# BW1097_EthernetSchDoc.net
KiCad netlist of a schematic drawn in Altium Designer
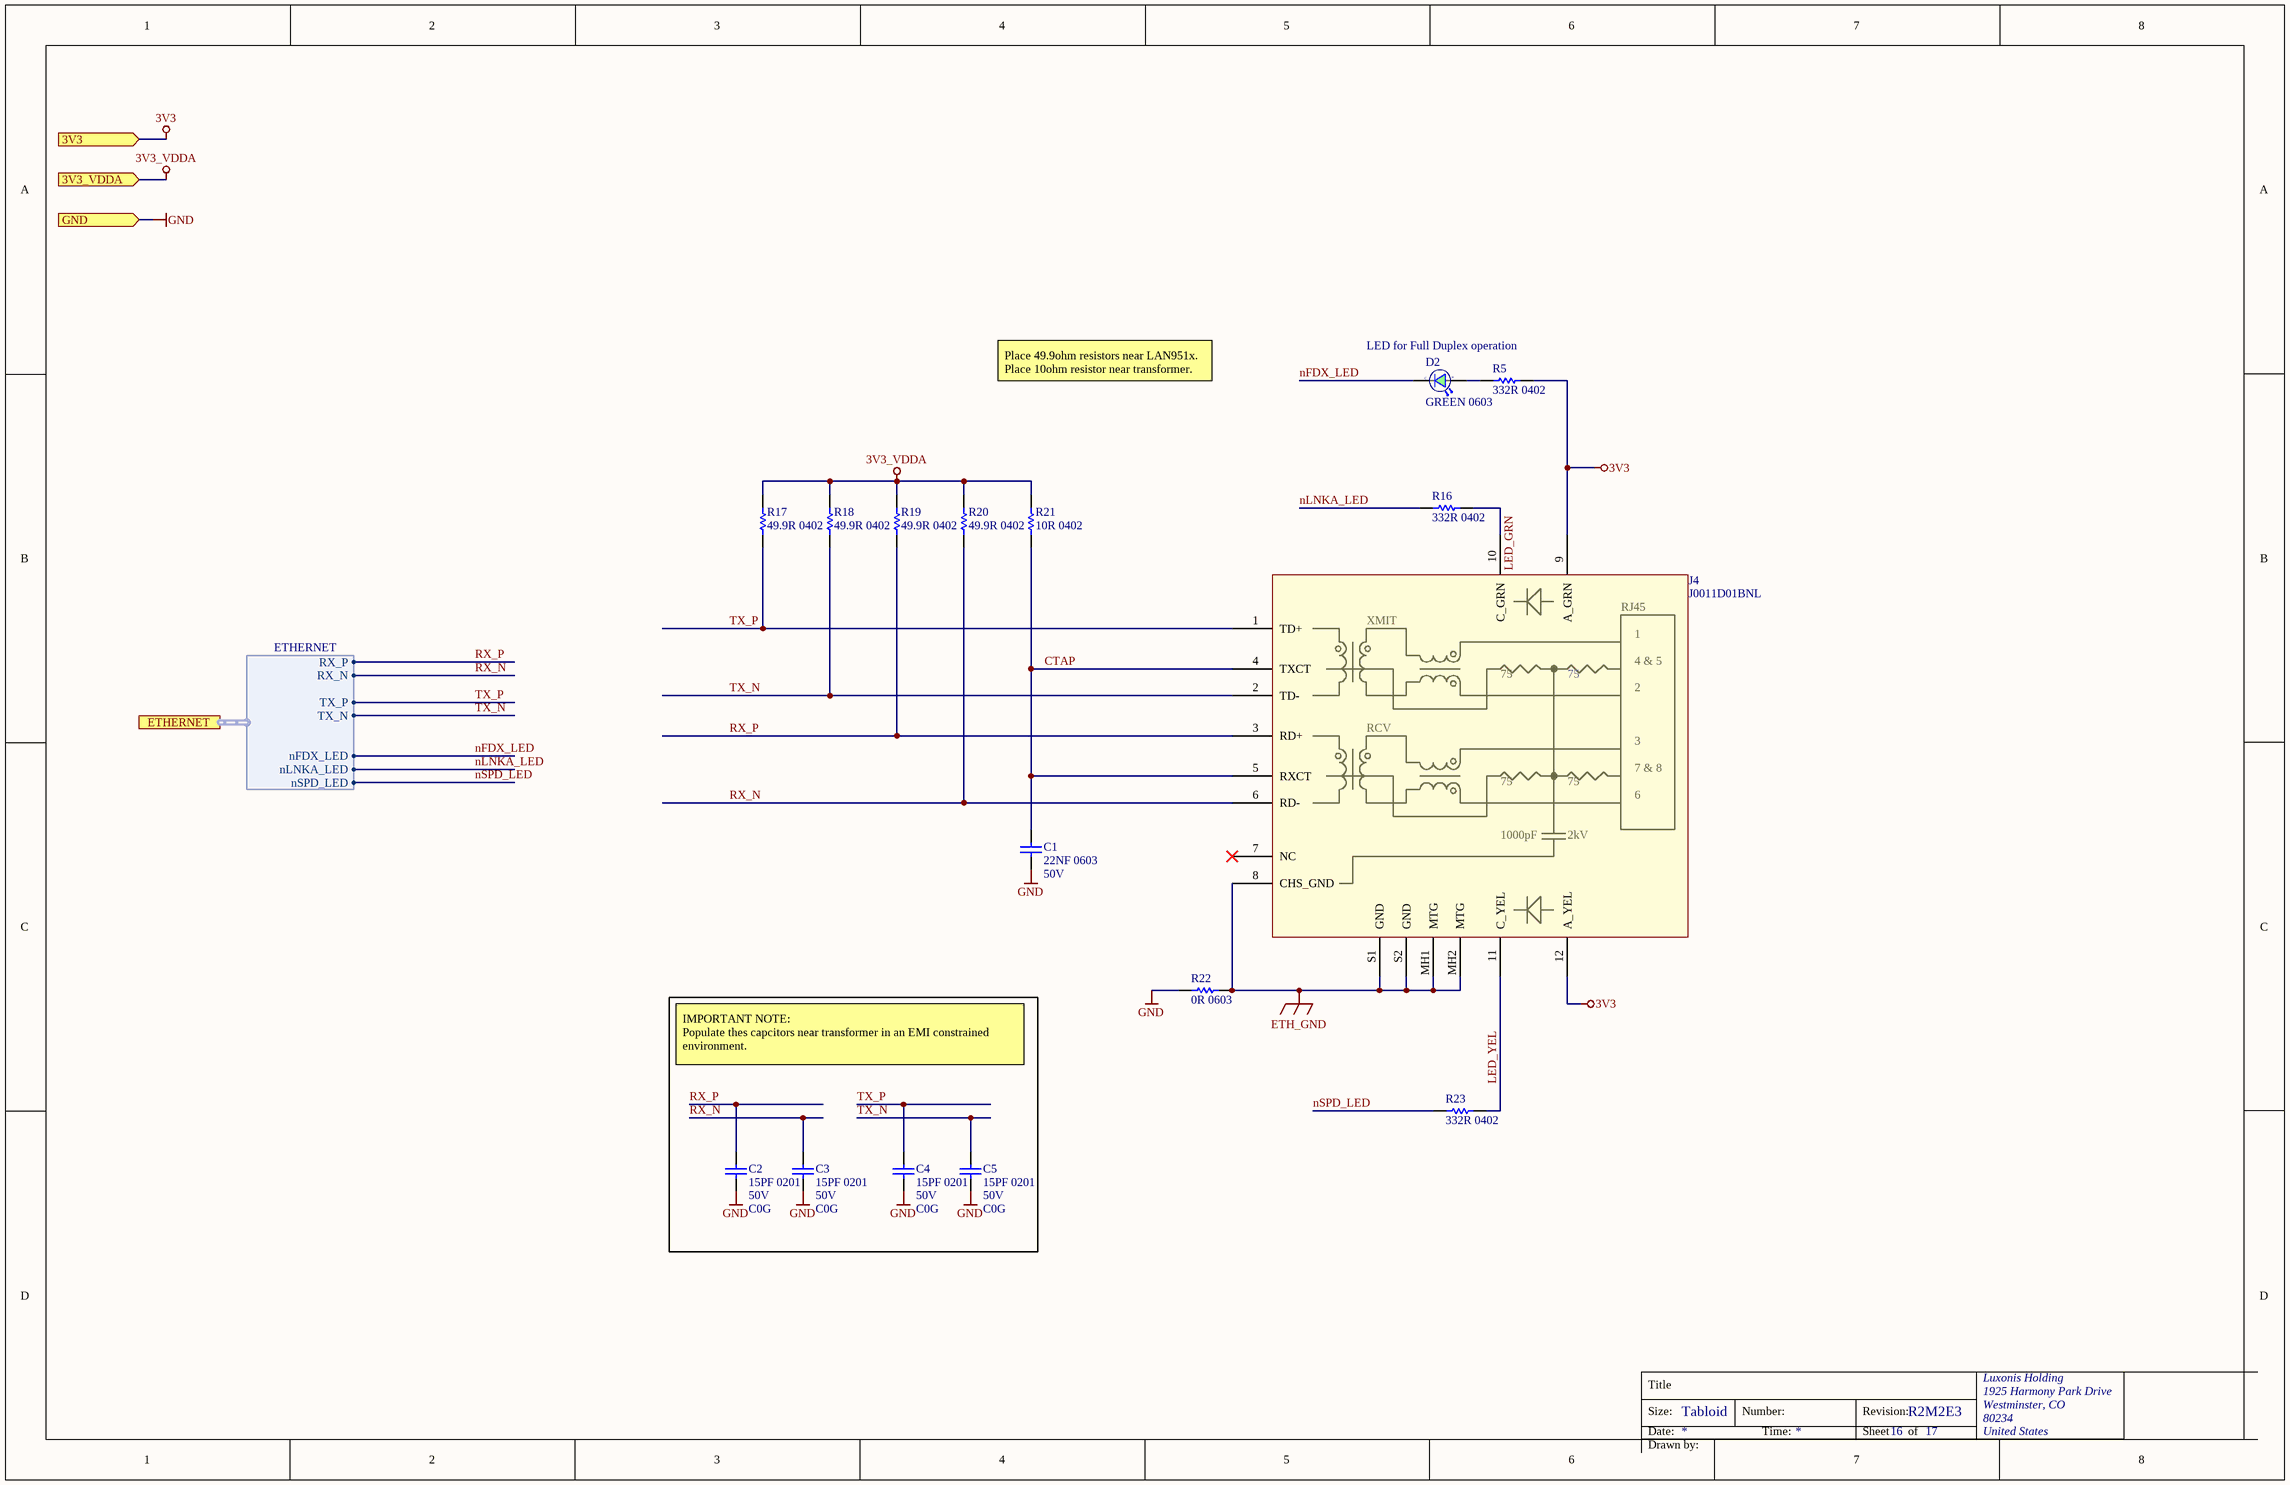
[diagram p0: BW1097_EthernetSchDoc.SchDoc]

(export (version "E")
  (design (tool "Eeschema 10.0.6"))
  (components
    (comp (ref "C1")
      (value "22NF 0603")
      (footprint "CAP_Altium_Vault_Generic:CAPC0603(1608)100_N")
      (description "CAP CER 0.022UF 50V X7R 0603")
      (fields (field (name "TOLERANCE") "10%") (field (name "VOLTAGE") "50V"))
      (libsource (lib "LuxonisMaster") (part "C0603C223K5RACTU"))
    )
    (comp (ref "C2")
      (value "15PF 0201")
      (footprint "CAP_Altium_Vault_Generic:CAPC0201(0603)33_L")
      (description "CAP CER 15PF 50V C0G/NP0 0201")
      (fields
        (field (name "TOLERANCE") "5%")
        (field (name "VOLTAGE") "50V")
        (field (name "DIELECTRIC") "C0G")
      )
      (libsource (lib "LuxonisMaster") (part "GRM0335C1H150JA01D"))
    )
    (comp (ref "C3")
      (value "15PF 0201")
      (footprint "CAP_Altium_Vault_Generic:CAPC0201(0603)33_L")
      (description "CAP CER 15PF 50V C0G/NP0 0201")
      (fields
        (field (name "TOLERANCE") "5%")
        (field (name "VOLTAGE") "50V")
        (field (name "DIELECTRIC") "C0G")
      )
      (libsource (lib "LuxonisMaster") (part "GRM0335C1H150JA01D"))
    )
    (comp (ref "C4")
      (value "15PF 0201")
      (footprint "CAP_Altium_Vault_Generic:CAPC0201(0603)33_L")
      (description "CAP CER 15PF 50V C0G/NP0 0201")
      (fields
        (field (name "TOLERANCE") "5%")
        (field (name "VOLTAGE") "50V")
        (field (name "DIELECTRIC") "C0G")
      )
      (libsource (lib "LuxonisMaster") (part "GRM0335C1H150JA01D"))
    )
    (comp (ref "C5")
      (value "15PF 0201")
      (footprint "CAP_Altium_Vault_Generic:CAPC0201(0603)33_L")
      (description "CAP CER 15PF 50V C0G/NP0 0201")
      (fields
        (field (name "TOLERANCE") "5%")
        (field (name "VOLTAGE") "50V")
        (field (name "DIELECTRIC") "C0G")
      )
      (libsource (lib "LuxonisMaster") (part "GRM0335C1H150JA01D"))
    )
    (comp (ref "D2")
      (value "GREEN 0603")
      (footprint "LuxonisMaster:SML_D1xx8W")
      (description "LED GREEN DIFFUSED 0603 SMD Green 572nm LED Indication - Discrete 2.2V 0603 (1608 Metric)")
      (fields (field (name "MANUFACTURER") "Rohm") (field (name "MANUFACTURER PART NUMBER") "SML-D12M8WT86"))
      (libsource (lib "LuxonisMaster") (part "SML-D12M8WT86"))
    )
    (comp (ref "J4")
      (value "J0011D01BNL")
      (footprint "LuxonisMaster:J0011D01BNL")
      (description "CONN MAGJACK 1PORT 100 BASE-TX 1 Port RJ45 Magjack Connector Through Hole 10/100 Base-TX, AutoMDIX")
      (libsource (lib "LuxonisMaster") (part "J0011D01BNL"))
    )
    (comp (ref "R5")
      (value "332R 0402")
      (footprint "RES_Altium_Vault_Generic:RESC0402(1005)_N")
      (description "RES SMD 332 OHM 1% 1/16W 0402")
      (fields (field (name "TOLERANCE") "1%"))
      (libsource (lib "LuxonisMaster") (part "RC0402FR-07332RL"))
    )
    (comp (ref "R16")
      (value "332R 0402")
      (footprint "RES_Altium_Vault_Generic:RESC0402(1005)_N")
      (description "RES SMD 332 OHM 1% 1/16W 0402")
      (fields (field (name "TOLERANCE") "1%"))
      (libsource (lib "LuxonisMaster") (part "RC0402FR-07332RL"))
    )
    (comp (ref "R17")
      (value "49.9R 0402")
      (footprint "RES_Altium_Vault_Generic:RESC0402(1005)_N")
      (description "RES SMD 49.9 OHM 1% 1/16W 0402")
      (fields (field (name "TOLERANCE") "1%"))
      (libsource (lib "LuxonisMaster") (part "RC0402FR-0749R9L"))
    )
    (comp (ref "R18")
      (value "49.9R 0402")
      (footprint "RES_Altium_Vault_Generic:RESC0402(1005)_N")
      (description "RES SMD 49.9 OHM 1% 1/16W 0402")
      (fields (field (name "TOLERANCE") "1%"))
      (libsource (lib "LuxonisMaster") (part "RC0402FR-0749R9L"))
    )
    (comp (ref "R19")
      (value "49.9R 0402")
      (footprint "RES_Altium_Vault_Generic:RESC0402(1005)_N")
      (description "RES SMD 49.9 OHM 1% 1/16W 0402")
      (fields (field (name "TOLERANCE") "1%"))
      (libsource (lib "LuxonisMaster") (part "RC0402FR-0749R9L"))
    )
    (comp (ref "R20")
      (value "49.9R 0402")
      (footprint "RES_Altium_Vault_Generic:RESC0402(1005)_N")
      (description "RES SMD 49.9 OHM 1% 1/16W 0402")
      (fields (field (name "TOLERANCE") "1%"))
      (libsource (lib "LuxonisMaster") (part "RC0402FR-0749R9L"))
    )
    (comp (ref "R21")
      (value "10R 0402")
      (footprint "RES_Altium_Vault_Generic:RESC0402(1005)_N")
      (description "RES SMD 10 OHM 1% 1/16W 0402")
      (fields (field (name "TOLERANCE") "1%"))
      (libsource (lib "LuxonisMaster") (part "RC0402FR-0710RL"))
    )
    (comp (ref "R22")
      (value "0R 0603")
      (footprint "RES_Altium_Vault_Generic:RESC0603(1608)_N")
      (fields (field (name "TOLERANCE") "5%"))
      (libsource (lib "LuxonisMaster") (part "CRCW06030000Z0EA"))
    )
    (comp (ref "R23")
      (value "332R 0402")
      (footprint "RES_Altium_Vault_Generic:RESC0402(1005)_N")
      (description "RES SMD 332 OHM 1% 1/16W 0402")
      (fields (field (name "TOLERANCE") "1%"))
      (libsource (lib "LuxonisMaster") (part "RC0402FR-07332RL"))
    )
  )
  (nets
    (net (code "2") (name "/CTAP") (class "Default")
      (node (ref "C1") (pin "2") (pinfunction "2_2") (pintype "passive"))
      (node (ref "J4") (pin "4") (pinfunction "TXCT_4") (pintype "passive"))
      (node (ref "J4") (pin "5") (pinfunction "RXCT_5") (pintype "passive"))
      (node (ref "R21") (pin "1") (pinfunction "1_1") (pintype "passive"))
    )
    (net (code "3") (name "/LED_GRN") (class "Default")
      (node (ref "J4") (pin "10") (pinfunction "C_GRN_10") (pintype "passive"))
      (node (ref "R16") (pin "2") (pinfunction "2_2") (pintype "passive"))
    )
    (net (code "4") (name "/LED_YEL") (class "Default")
      (node (ref "J4") (pin "11") (pinfunction "C_YEL_11") (pintype "passive"))
      (node (ref "R23") (pin "2") (pinfunction "2_2") (pintype "passive"))
    )
    (net (code "5") (name "/RX_N") (class "Default")
      (node (ref "C3") (pin "2") (pinfunction "2_2") (pintype "passive"))
      (node (ref "J4") (pin "6") (pinfunction "RD-_6") (pintype "passive"))
      (node (ref "R20") (pin "1") (pinfunction "1_1") (pintype "passive"))
    )
    (net (code "6") (name "/RX_P") (class "Default")
      (node (ref "C2") (pin "2") (pinfunction "2_2") (pintype "passive"))
      (node (ref "J4") (pin "3") (pinfunction "RD+_3") (pintype "passive"))
      (node (ref "R19") (pin "1") (pinfunction "1_1") (pintype "passive"))
    )
    (net (code "7") (name "/TX_N") (class "Default")
      (node (ref "C5") (pin "2") (pinfunction "2_2") (pintype "passive"))
      (node (ref "J4") (pin "2") (pinfunction "TD-_2") (pintype "passive"))
      (node (ref "R18") (pin "1") (pinfunction "1_1") (pintype "passive"))
    )
    (net (code "8") (name "/TX_P") (class "Default")
      (node (ref "C4") (pin "2") (pinfunction "2_2") (pintype "passive"))
      (node (ref "J4") (pin "1") (pinfunction "TD+_1") (pintype "passive"))
      (node (ref "R17") (pin "1") (pinfunction "1_1") (pintype "passive"))
    )
    (net (code "9") (name "/nFDX_LED") (class "Default")
      (node (ref "D2") (pin "1") (pinfunction "C_1") (pintype "passive"))
    )
    (net (code "10") (name "/nLNKA_LED") (class "Default")
      (node (ref "R16") (pin "1") (pinfunction "1_1") (pintype "passive"))
    )
    (net (code "11") (name "/nSPD_LED") (class "Default")
      (node (ref "R23") (pin "1") (pinfunction "1_1") (pintype "passive"))
    )
    (net (code "13") (name "3V3") (class "Default")
      (node (ref "J4") (pin "12") (pinfunction "A_YEL_12") (pintype "passive"))
      (node (ref "J4") (pin "9") (pinfunction "A_GRN_9") (pintype "passive"))
      (node (ref "R5") (pin "2") (pinfunction "2_2") (pintype "passive"))
    )
    (net (code "14") (name "3V3_VDDA") (class "Default")
      (node (ref "R17") (pin "2") (pinfunction "2_2") (pintype "passive"))
      (node (ref "R18") (pin "2") (pinfunction "2_2") (pintype "passive"))
      (node (ref "R19") (pin "2") (pinfunction "2_2") (pintype "passive"))
      (node (ref "R20") (pin "2") (pinfunction "2_2") (pintype "passive"))
      (node (ref "R21") (pin "2") (pinfunction "2_2") (pintype "passive"))
    )
    (net (code "15") (name "ETH_GND") (class "Default")
      (node (ref "J4") (pin "8") (pinfunction "CHS_GND_8") (pintype "passive"))
      (node (ref "J4") (pin "MH1") (pinfunction "MTG_MH1") (pintype "passive"))
      (node (ref "J4") (pin "MH2") (pinfunction "MTG_MH2") (pintype "passive"))
      (node (ref "J4") (pin "S1") (pinfunction "GND_S1") (pintype "passive"))
      (node (ref "J4") (pin "S2") (pinfunction "GND_S2") (pintype "passive"))
      (node (ref "R22") (pin "2") (pinfunction "2_2") (pintype "passive"))
    )
    (net (code "16") (name "GND") (class "Default")
      (node (ref "C1") (pin "1") (pinfunction "1_1") (pintype "passive"))
      (node (ref "C2") (pin "1") (pinfunction "1_1") (pintype "passive"))
      (node (ref "C3") (pin "1") (pinfunction "1_1") (pintype "passive"))
      (node (ref "C4") (pin "1") (pinfunction "1_1") (pintype "passive"))
      (node (ref "C5") (pin "1") (pinfunction "1_1") (pintype "passive"))
      (node (ref "R22") (pin "1") (pinfunction "1_1") (pintype "passive"))
    )
    (net (code "17") (name "Net-(D2-A)") (class "Default")
      (node (ref "D2") (pin "2") (pinfunction "A_2") (pintype "passive"))
      (node (ref "R5") (pin "1") (pinfunction "1_1") (pintype "passive"))
    )
    (net (code "18") (name "unconnected-(J4-NC-Pad7)") (class "Default")
      (node (ref "J4") (pin "7") (pinfunction "NC_7") (pintype "passive+no_connect"))
    )
    (net (code "19") (name "unconnected-(J4-Pad1)") (class "Default")
      (node (ref "J4") (pin "1") (pinfunction "1_1") (pintype "passive"))
    )
    (net (code "20") (name "unconnected-(J4-Pad2)") (class "Default")
      (node (ref "J4") (pin "2") (pinfunction "2_2") (pintype "passive"))
    )
  )
)
